# TricolorShield.net
KiCad netlist of a schematic drawn in EAGLE
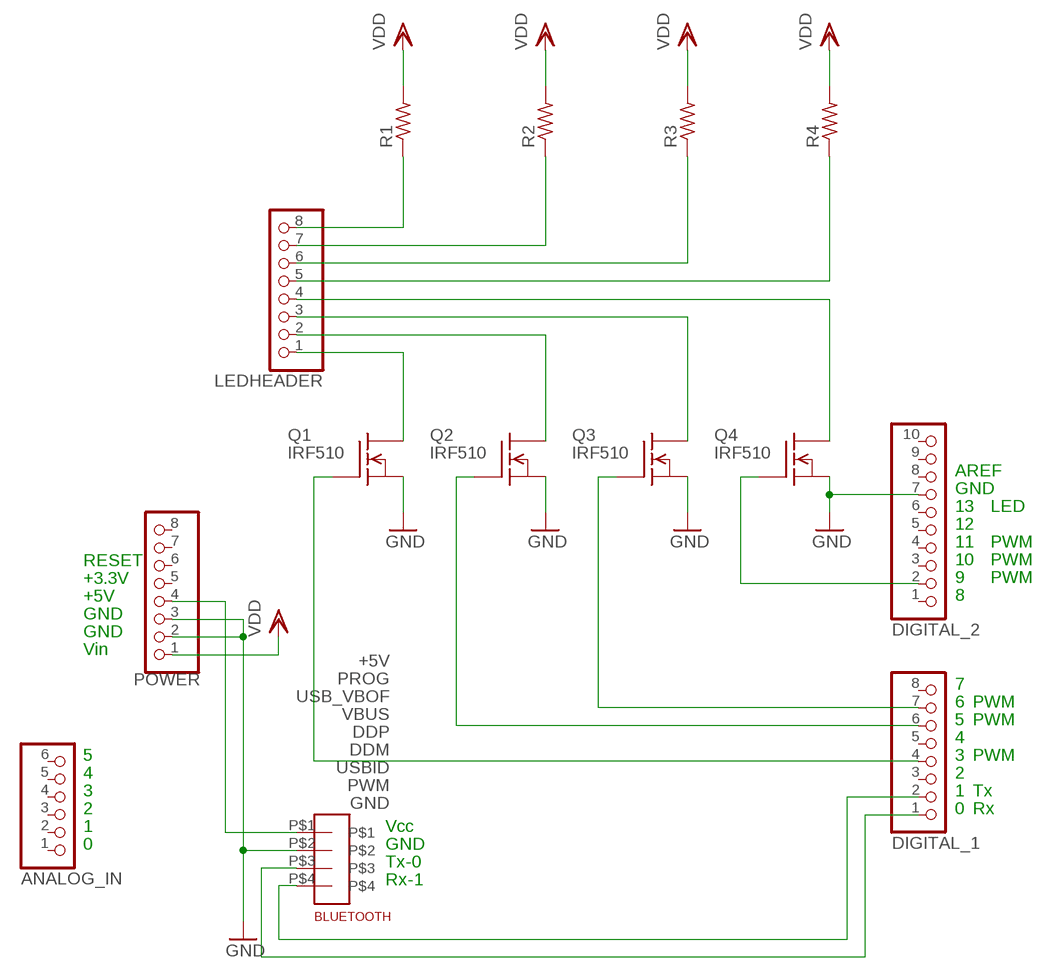
[diagram p0: schematic, sheet 1]

(export (version "E")
  (design (tool "Eeschema 10.0.6"))
  (components
    (comp (ref "ANALOG_IN")
      (value "PINHD-1X6TH")
      (footprint "eagle-import:1X06-TH")
      (libsource (lib "eagle-import") (part "PINHD-1X6TH"))
    )
    (comp (ref "BLUETOOTH")
      (value "4PADS_ROBBIE")
      (footprint "eagle-import:1X04_ROBBIE")
      (libsource (lib "eagle-import") (part "4PADS_ROBBIE"))
    )
    (comp (ref "DIGITAL_1")
      (value "PINHD-1X8TH")
      (footprint "eagle-import:1X08-TH")
      (libsource (lib "eagle-import") (part "PINHD-1X8TH"))
    )
    (comp (ref "DIGITAL_2")
      (value "PINHD-1X10TH")
      (footprint "eagle-import:1X10-TH")
      (libsource (lib "eagle-import") (part "PINHD-1X10TH"))
    )
    (comp (ref "LEDHEADER")
      (value "PINHD-1X8TH")
      (footprint "eagle-import:1X08-TH")
      (libsource (lib "eagle-import") (part "PINHD-1X8TH"))
    )
    (comp (ref "POWER")
      (value "PINHD-1X8TH")
      (footprint "eagle-import:1X08-TH")
      (libsource (lib "eagle-import") (part "PINHD-1X8TH"))
    )
    (comp (ref "Q1")
      (value "IRF510")
      (footprint "eagle-import:TO220")
      (libsource (lib "eagle-import") (part "IRF510"))
    )
    (comp (ref "Q2")
      (value "IRF510")
      (footprint "eagle-import:TO220")
      (libsource (lib "eagle-import") (part "IRF510"))
    )
    (comp (ref "Q3")
      (value "IRF510")
      (footprint "eagle-import:TO220")
      (libsource (lib "eagle-import") (part "IRF510"))
    )
    (comp (ref "Q4")
      (value "IRF510")
      (footprint "eagle-import:TO220")
      (libsource (lib "eagle-import") (part "IRF510"))
    )
    (comp (ref "R1")
      (value "R-US_0922/22")
      (footprint "eagle-import:0922_22")
      (libsource (lib "eagle-import") (part "R-US_0922/22"))
    )
    (comp (ref "R2")
      (value "R-US_0922/22")
      (footprint "eagle-import:0922_22")
      (libsource (lib "eagle-import") (part "R-US_0922/22"))
    )
    (comp (ref "R3")
      (value "R-US_0922/22")
      (footprint "eagle-import:0922_22")
      (libsource (lib "eagle-import") (part "R-US_0922/22"))
    )
    (comp (ref "R4")
      (value "R-US_0922/22")
      (footprint "eagle-import:0922_22")
      (libsource (lib "eagle-import") (part "R-US_0922/22"))
    )
  )
  (nets
    (net (code "1") (name "GND") (class "Default")
      (node (ref "BLUETOOTH") (pin "P$2") (pinfunction "P$2_P$2") (pintype "bidirectional"))
      (node (ref "DIGITAL_2") (pin "7") (pinfunction "7_7") (pintype "passive"))
      (node (ref "POWER") (pin "2") (pinfunction "2_2") (pintype "passive"))
      (node (ref "POWER") (pin "3") (pinfunction "3_3") (pintype "passive"))
      (node (ref "Q1") (pin "3") (pinfunction "S_3") (pintype "passive"))
      (node (ref "Q2") (pin "3") (pinfunction "S_3") (pintype "passive"))
      (node (ref "Q3") (pin "3") (pinfunction "S_3") (pintype "passive"))
      (node (ref "Q4") (pin "3") (pinfunction "S_3") (pintype "passive"))
    )
    (net (code "2") (name "Net-(BLUETOOTH-PadP$1)") (class "Default")
      (node (ref "BLUETOOTH") (pin "P$1") (pinfunction "P$1_P$1") (pintype "bidirectional"))
      (node (ref "POWER") (pin "4") (pinfunction "4_4") (pintype "passive"))
    )
    (net (code "3") (name "Net-(BLUETOOTH-PadP$3)") (class "Default")
      (node (ref "BLUETOOTH") (pin "P$3") (pinfunction "P$3_P$3") (pintype "bidirectional"))
      (node (ref "DIGITAL_1") (pin "1") (pinfunction "1_1") (pintype "passive"))
    )
    (net (code "4") (name "Net-(BLUETOOTH-PadP$4)") (class "Default")
      (node (ref "BLUETOOTH") (pin "P$4") (pinfunction "P$4_P$4") (pintype "bidirectional"))
      (node (ref "DIGITAL_1") (pin "2") (pinfunction "2_2") (pintype "passive"))
    )
    (net (code "5") (name "Net-(LEDHEADER-Pad5)") (class "Default")
      (node (ref "LEDHEADER") (pin "5") (pinfunction "5_5") (pintype "passive"))
      (node (ref "R4") (pin "1") (pinfunction "1_1") (pintype "passive"))
    )
    (net (code "6") (name "Net-(LEDHEADER-Pad6)") (class "Default")
      (node (ref "LEDHEADER") (pin "6") (pinfunction "6_6") (pintype "passive"))
      (node (ref "R3") (pin "1") (pinfunction "1_1") (pintype "passive"))
    )
    (net (code "7") (name "Net-(LEDHEADER-Pad7)") (class "Default")
      (node (ref "LEDHEADER") (pin "7") (pinfunction "7_7") (pintype "passive"))
      (node (ref "R2") (pin "1") (pinfunction "1_1") (pintype "passive"))
    )
    (net (code "8") (name "Net-(LEDHEADER-Pad8)") (class "Default")
      (node (ref "LEDHEADER") (pin "8") (pinfunction "8_8") (pintype "passive"))
      (node (ref "R1") (pin "1") (pinfunction "1_1") (pintype "passive"))
    )
    (net (code "9") (name "Net-(Q1-D)") (class "Default")
      (node (ref "LEDHEADER") (pin "1") (pinfunction "1_1") (pintype "passive"))
      (node (ref "Q1") (pin "2") (pinfunction "D_2") (pintype "passive"))
    )
    (net (code "10") (name "Net-(Q1-G)") (class "Default")
      (node (ref "DIGITAL_1") (pin "4") (pinfunction "4_4") (pintype "passive"))
      (node (ref "Q1") (pin "1") (pinfunction "G_1") (pintype "passive"))
    )
    (net (code "11") (name "Net-(Q2-D)") (class "Default")
      (node (ref "LEDHEADER") (pin "2") (pinfunction "2_2") (pintype "passive"))
      (node (ref "Q2") (pin "2") (pinfunction "D_2") (pintype "passive"))
    )
    (net (code "12") (name "Net-(Q2-G)") (class "Default")
      (node (ref "DIGITAL_1") (pin "6") (pinfunction "6_6") (pintype "passive"))
      (node (ref "Q2") (pin "1") (pinfunction "G_1") (pintype "passive"))
    )
    (net (code "13") (name "Net-(Q3-D)") (class "Default")
      (node (ref "LEDHEADER") (pin "3") (pinfunction "3_3") (pintype "passive"))
      (node (ref "Q3") (pin "2") (pinfunction "D_2") (pintype "passive"))
    )
    (net (code "14") (name "Net-(Q3-G)") (class "Default")
      (node (ref "DIGITAL_1") (pin "7") (pinfunction "7_7") (pintype "passive"))
      (node (ref "Q3") (pin "1") (pinfunction "G_1") (pintype "passive"))
    )
    (net (code "15") (name "Net-(Q4-D)") (class "Default")
      (node (ref "LEDHEADER") (pin "4") (pinfunction "4_4") (pintype "passive"))
      (node (ref "Q4") (pin "2") (pinfunction "D_2") (pintype "passive"))
    )
    (net (code "16") (name "Net-(Q4-G)") (class "Default")
      (node (ref "DIGITAL_2") (pin "2") (pinfunction "2_2") (pintype "passive"))
      (node (ref "Q4") (pin "1") (pinfunction "G_1") (pintype "passive"))
    )
    (net (code "17") (name "VDD") (class "Default")
      (node (ref "POWER") (pin "1") (pinfunction "1_1") (pintype "passive"))
      (node (ref "R1") (pin "2") (pinfunction "2_2") (pintype "passive"))
      (node (ref "R2") (pin "2") (pinfunction "2_2") (pintype "passive"))
      (node (ref "R3") (pin "2") (pinfunction "2_2") (pintype "passive"))
      (node (ref "R4") (pin "2") (pinfunction "2_2") (pintype "passive"))
    )
    (net (code "18") (name "unconnected-(ANALOG_IN-Pad1)") (class "Default")
      (node (ref "ANALOG_IN") (pin "1") (pinfunction "1_1") (pintype "passive"))
    )
    (net (code "19") (name "unconnected-(ANALOG_IN-Pad2)") (class "Default")
      (node (ref "ANALOG_IN") (pin "2") (pinfunction "2_2") (pintype "passive"))
    )
    (net (code "20") (name "unconnected-(ANALOG_IN-Pad3)") (class "Default")
      (node (ref "ANALOG_IN") (pin "3") (pinfunction "3_3") (pintype "passive"))
    )
    (net (code "21") (name "unconnected-(ANALOG_IN-Pad4)") (class "Default")
      (node (ref "ANALOG_IN") (pin "4") (pinfunction "4_4") (pintype "passive"))
    )
    (net (code "22") (name "unconnected-(ANALOG_IN-Pad5)") (class "Default")
      (node (ref "ANALOG_IN") (pin "5") (pinfunction "5_5") (pintype "passive"))
    )
    (net (code "23") (name "unconnected-(ANALOG_IN-Pad6)") (class "Default")
      (node (ref "ANALOG_IN") (pin "6") (pinfunction "6_6") (pintype "passive"))
    )
    (net (code "24") (name "unconnected-(DIGITAL_1-Pad3)") (class "Default")
      (node (ref "DIGITAL_1") (pin "3") (pinfunction "3_3") (pintype "passive"))
    )
    (net (code "25") (name "unconnected-(DIGITAL_1-Pad5)") (class "Default")
      (node (ref "DIGITAL_1") (pin "5") (pinfunction "5_5") (pintype "passive"))
    )
    (net (code "26") (name "unconnected-(DIGITAL_1-Pad8)") (class "Default")
      (node (ref "DIGITAL_1") (pin "8") (pinfunction "8_8") (pintype "passive"))
    )
    (net (code "27") (name "unconnected-(DIGITAL_2-Pad1)") (class "Default")
      (node (ref "DIGITAL_2") (pin "1") (pinfunction "1_1") (pintype "passive"))
    )
    (net (code "28") (name "unconnected-(DIGITAL_2-Pad3)") (class "Default")
      (node (ref "DIGITAL_2") (pin "3") (pinfunction "3_3") (pintype "passive"))
    )
    (net (code "29") (name "unconnected-(DIGITAL_2-Pad4)") (class "Default")
      (node (ref "DIGITAL_2") (pin "4") (pinfunction "4_4") (pintype "passive"))
    )
    (net (code "30") (name "unconnected-(DIGITAL_2-Pad5)") (class "Default")
      (node (ref "DIGITAL_2") (pin "5") (pinfunction "5_5") (pintype "passive"))
    )
    (net (code "31") (name "unconnected-(DIGITAL_2-Pad6)") (class "Default")
      (node (ref "DIGITAL_2") (pin "6") (pinfunction "6_6") (pintype "passive"))
    )
    (net (code "32") (name "unconnected-(DIGITAL_2-Pad8)") (class "Default")
      (node (ref "DIGITAL_2") (pin "8") (pinfunction "8_8") (pintype "passive"))
    )
    (net (code "33") (name "unconnected-(DIGITAL_2-Pad9)") (class "Default")
      (node (ref "DIGITAL_2") (pin "9") (pinfunction "9_9") (pintype "passive"))
    )
    (net (code "34") (name "unconnected-(DIGITAL_2-Pad10)") (class "Default")
      (node (ref "DIGITAL_2") (pin "10") (pinfunction "10_10") (pintype "passive"))
    )
    (net (code "35") (name "unconnected-(POWER-Pad5)") (class "Default")
      (node (ref "POWER") (pin "5") (pinfunction "5_5") (pintype "passive"))
    )
    (net (code "36") (name "unconnected-(POWER-Pad6)") (class "Default")
      (node (ref "POWER") (pin "6") (pinfunction "6_6") (pintype "passive"))
    )
    (net (code "37") (name "unconnected-(POWER-Pad7)") (class "Default")
      (node (ref "POWER") (pin "7") (pinfunction "7_7") (pintype "passive"))
    )
    (net (code "38") (name "unconnected-(POWER-Pad8)") (class "Default")
      (node (ref "POWER") (pin "8") (pinfunction "8_8") (pintype "passive"))
    )
  )
)
